# Controls.net
KiCad netlist of a schematic drawn in Altium Designer
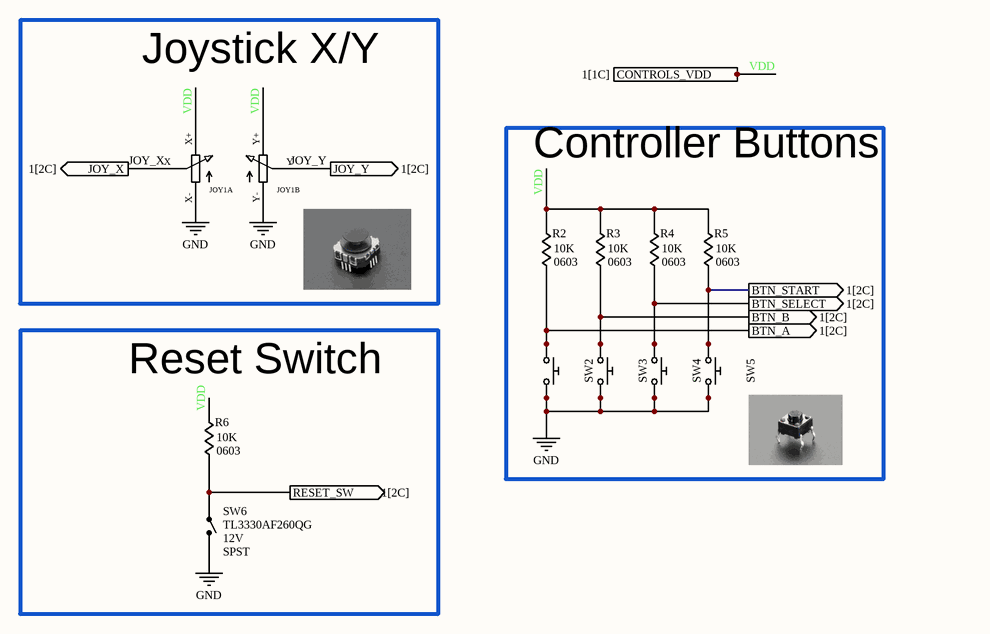
[diagram p0: Controls.SchDoc]

(export (version "E")
  (design (tool "Eeschema 10.0.6"))
  (components
    (comp (ref "JOY1")
      (value "CTRL-JOYSTICK_ANALOG_XY")
      (footprint "PCB-JOYSTICK-ANALOG_MINITHM")
      (description "2-Axis analog joystick")
      (libsource (lib "Animal Inspired Movement and Robotics Lab (AIMRL)") (part "SCH-JOYSTICK-ANALOG_XY"))
    )
    (comp (ref "R2")
      (value "10K")
      (footprint "0603")
      (description "Generic (no part number) 0603 surface mount resistor")
      (fields (field (name "Comment") "RES-SMD-0603"))
      (libsource (lib "Animal Inspired Movement and Robotics Lab (AIMRL)") (part "SCH-RES-SMD-0603"))
    )
    (comp (ref "R3")
      (value "10K")
      (footprint "0603")
      (description "Generic (no part number) 0603 surface mount resistor")
      (fields (field (name "Comment") "RES-SMD-0603"))
      (libsource (lib "Animal Inspired Movement and Robotics Lab (AIMRL)") (part "SCH-RES-SMD-0603"))
    )
    (comp (ref "R4")
      (value "10K")
      (footprint "0603")
      (description "Generic (no part number) 0603 surface mount resistor")
      (fields (field (name "Comment") "RES-SMD-0603"))
      (libsource (lib "Animal Inspired Movement and Robotics Lab (AIMRL)") (part "SCH-RES-SMD-0603"))
    )
    (comp (ref "R5")
      (value "10K")
      (footprint "0603")
      (description "Generic (no part number) 0603 surface mount resistor")
      (fields (field (name "Comment") "RES-SMD-0603"))
      (libsource (lib "Animal Inspired Movement and Robotics Lab (AIMRL)") (part "SCH-RES-SMD-0603"))
    )
    (comp (ref "R6")
      (value "10K")
      (footprint "0603")
      (description "Generic (no part number) 0603 surface mount resistor")
      (fields (field (name "Comment") "RES-SMD-0603"))
      (libsource (lib "Animal Inspired Movement and Robotics Lab (AIMRL)") (part "SCH-RES-SMD-0603"))
    )
    (comp (ref "SW2")
      (value "SWITCH-SMD-SMT-6MM")
      (footprint "PCB-SMD-SWITCH-6MM")
      (description "6mm diameter tactile switch.")
      (fields
        (field (name "LIBRARYNAME") "Adafruit PyGamer")
        (field (name "SOURCE") "Adafruit PyGamer.SCHLIB")
      )
      (libsource (lib "Animal Inspired Movement and Robotics Lab (AIMRL)") (part "PCB-SWITCH_TACT_SMT_6MM"))
    )
    (comp (ref "SW3")
      (value "SWITCH-SMD-SMT-6MM")
      (footprint "PCB-SMD-SWITCH-6MM")
      (description "6mm diameter tactile switch.")
      (fields
        (field (name "LIBRARYNAME") "Adafruit PyGamer")
        (field (name "SOURCE") "Adafruit PyGamer.SCHLIB")
      )
      (libsource (lib "Animal Inspired Movement and Robotics Lab (AIMRL)") (part "PCB-SWITCH_TACT_SMT_6MM"))
    )
    (comp (ref "SW4")
      (value "SWITCH-SMD-SMT-6MM")
      (footprint "PCB-SMD-SWITCH-6MM")
      (description "6mm diameter tactile switch.")
      (fields
        (field (name "LIBRARYNAME") "Adafruit PyGamer")
        (field (name "SOURCE") "Adafruit PyGamer.SCHLIB")
      )
      (libsource (lib "Animal Inspired Movement and Robotics Lab (AIMRL)") (part "PCB-SWITCH_TACT_SMT_6MM"))
    )
    (comp (ref "SW5")
      (value "SWITCH-SMD-SMT-6MM")
      (footprint "PCB-SMD-SWITCH-6MM")
      (description "6mm diameter tactile switch.")
      (fields
        (field (name "LIBRARYNAME") "Adafruit PyGamer")
        (field (name "SOURCE") "Adafruit PyGamer.SCHLIB")
      )
      (libsource (lib "Animal Inspired Movement and Robotics Lab (AIMRL)") (part "PCB-SWITCH_TACT_SMT_6MM"))
    )
    (comp (ref "SW6")
      (value "SWITCH-SPST-TACT-RA")
      (footprint "PCB-SPST-TACTILE-RA")
      (description "Switch Tactile N.O. SPST Rectangular Button Gull Wing 0.05A 12VDC 2.55N SMD")
      (fields
        (field (name "VOLTAGE RATING (DC)") "12V")
        (field (name "THROW CONFIGURATION") "SPST")
        (field (name "PART NUMBER") "TL3330AF260QG")
      )
      (libsource (lib "Animal Inspired Movement and Robotics Lab (AIMRL)") (part "SCH-SWITCH-SPST"))
    )
  )
  (nets
    (net (code "1") (name "/BTN_A") (class "Default")
      (node (ref "R2") (pin "1") (pinfunction "1_1") (pintype "passive"))
      (node (ref "SW2") (pin "A") (pinfunction "P_A") (pintype "passive"))
      (node (ref "SW2") (pin "A'") (pinfunction "P1_A'") (pintype "passive"))
    )
    (net (code "2") (name "/BTN_B") (class "Default")
      (node (ref "R3") (pin "1") (pinfunction "1_1") (pintype "passive"))
      (node (ref "SW3") (pin "A") (pinfunction "P_A") (pintype "passive"))
      (node (ref "SW3") (pin "A'") (pinfunction "P1_A'") (pintype "passive"))
    )
    (net (code "3") (name "/BTN_SELECT") (class "Default")
      (node (ref "R4") (pin "1") (pinfunction "1_1") (pintype "passive"))
      (node (ref "SW4") (pin "A") (pinfunction "P_A") (pintype "passive"))
      (node (ref "SW4") (pin "A'") (pinfunction "P1_A'") (pintype "passive"))
    )
    (net (code "4") (name "/BTN_START") (class "Default")
      (node (ref "R5") (pin "1") (pinfunction "1_1") (pintype "passive"))
      (node (ref "SW5") (pin "A") (pinfunction "P_A") (pintype "passive"))
      (node (ref "SW5") (pin "A'") (pinfunction "P1_A'") (pintype "passive"))
    )
    (net (code "5") (name "/JOY_X") (class "Default")
      (node (ref "JOY1") (pin "X") (pinfunction "S_X") (pintype "passive"))
    )
    (net (code "6") (name "/JOY_Y") (class "Default")
      (node (ref "JOY1") (pin "Y") (pinfunction "S_Y") (pintype "passive"))
    )
    (net (code "7") (name "/RESET_SW") (class "Default")
      (node (ref "R6") (pin "1") (pinfunction "1_1") (pintype "passive"))
      (node (ref "SW6") (pin "1") (pinfunction "P_1") (pintype "passive"))
    )
    (net (code "8") (name "/VDD") (class "Default")
      (node (ref "JOY1") (pin "X+") (pinfunction "E_X+") (pintype "passive"))
      (node (ref "JOY1") (pin "Y+") (pinfunction "E_Y+") (pintype "passive"))
      (node (ref "R2") (pin "2") (pinfunction "2_2") (pintype "passive"))
      (node (ref "R3") (pin "2") (pinfunction "2_2") (pintype "passive"))
      (node (ref "R4") (pin "2") (pinfunction "2_2") (pintype "passive"))
      (node (ref "R5") (pin "2") (pinfunction "2_2") (pintype "passive"))
      (node (ref "R6") (pin "2") (pinfunction "2_2") (pintype "passive"))
    )
    (net (code "9") (name "GND") (class "Default")
      (node (ref "JOY1") (pin "X-") (pinfunction "A_X-") (pintype "passive"))
      (node (ref "JOY1") (pin "Y-") (pinfunction "A_Y-") (pintype "passive"))
      (node (ref "SW2") (pin "B") (pinfunction "S_B") (pintype "passive"))
      (node (ref "SW2") (pin "B'") (pinfunction "S1_B'") (pintype "passive"))
      (node (ref "SW3") (pin "B") (pinfunction "S_B") (pintype "passive"))
      (node (ref "SW3") (pin "B'") (pinfunction "S1_B'") (pintype "passive"))
      (node (ref "SW4") (pin "B") (pinfunction "S_B") (pintype "passive"))
      (node (ref "SW4") (pin "B'") (pinfunction "S1_B'") (pintype "passive"))
      (node (ref "SW5") (pin "B") (pinfunction "S_B") (pintype "passive"))
      (node (ref "SW5") (pin "B'") (pinfunction "S1_B'") (pintype "passive"))
      (node (ref "SW6") (pin "2") (pinfunction "S_2") (pintype "passive"))
    )
    (net (code "10") (name "Net-(SW6-MT-PadMT1)") (class "Default")
      (node (ref "SW6") (pin "MT1") (pinfunction "MT_MT1") (pintype "passive"))
      (node (ref "SW6") (pin "MT2") (pinfunction "MT_MT2") (pintype "passive"))
    )
  )
)
